# mainBoard.net
KiCad netlist of a schematic drawn in EAGLE
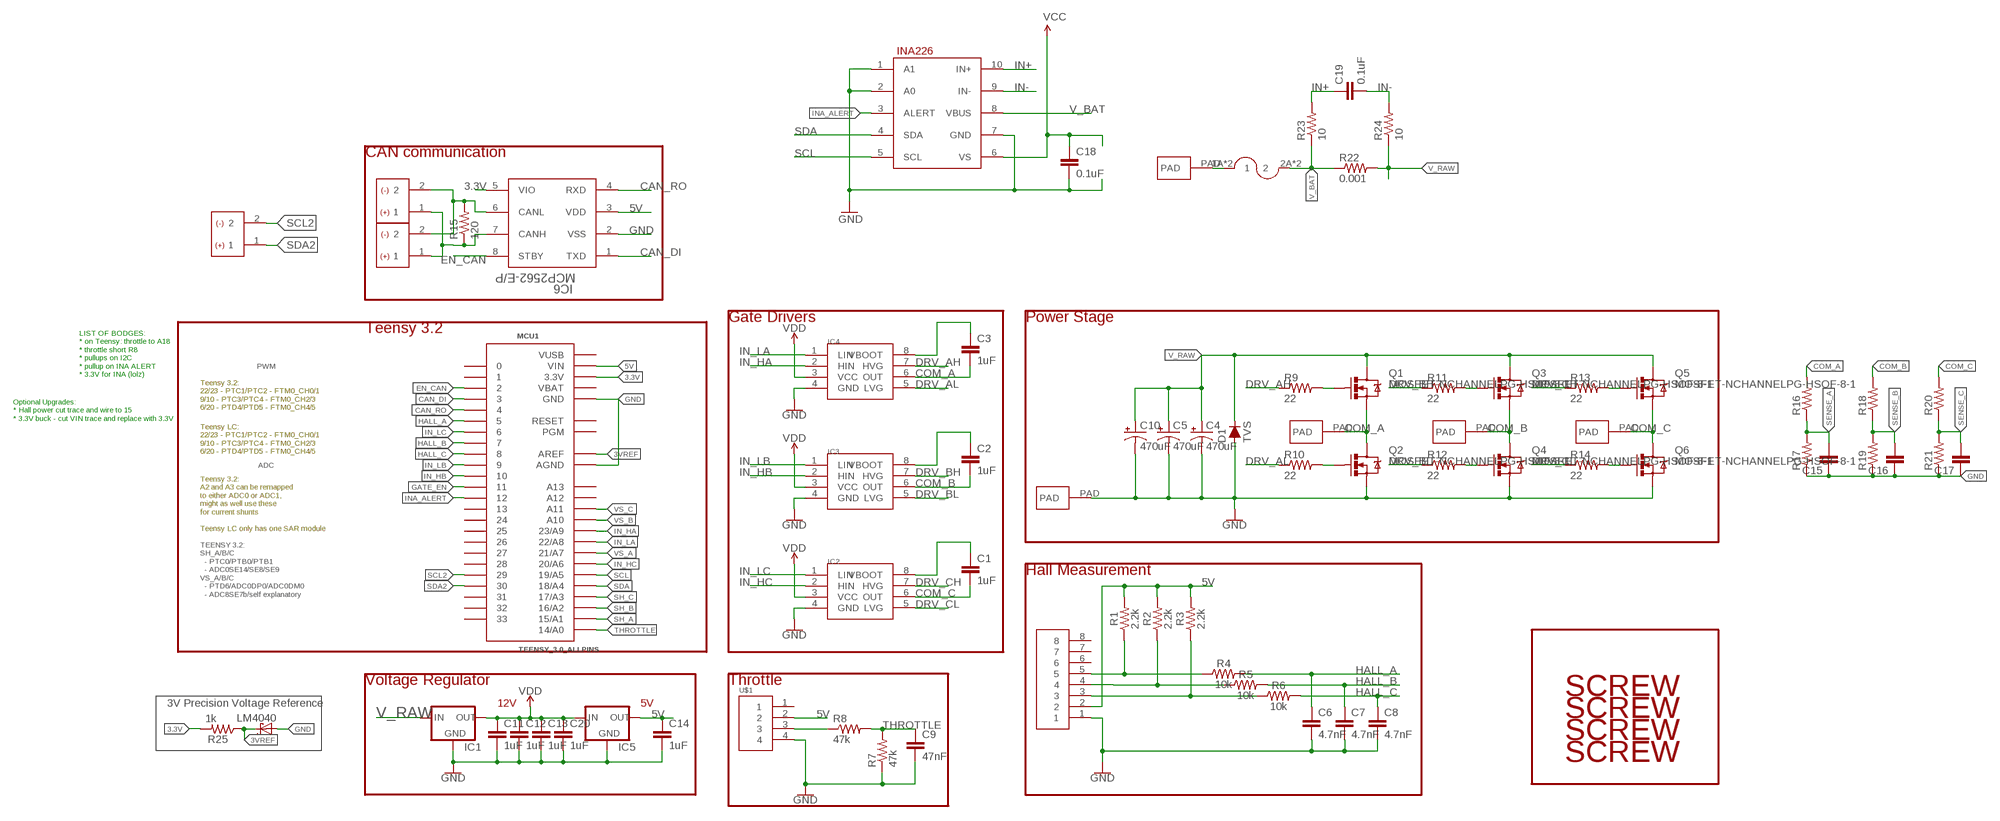
[diagram p0: schematic, sheet 1, part 1 of 2]
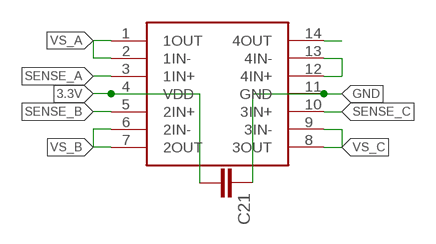
[diagram p1: schematic, sheet 1, part 2 of 2]

(export (version "E")
  (design (tool "Eeschema 10.0.6"))
  (components
    (comp (ref "C1")
      (value "1uF")
      (footprint "eagle-import:CAP-PTH-SMALL-KIT")
      (libsource (lib "eagle-import") (part "CAPKIT"))
    )
    (comp (ref "C2")
      (value "1uF")
      (footprint "eagle-import:CAP-PTH-SMALL-KIT")
      (libsource (lib "eagle-import") (part "CAPKIT"))
    )
    (comp (ref "C3")
      (value "1uF")
      (footprint "eagle-import:CAP-PTH-SMALL-KIT")
      (libsource (lib "eagle-import") (part "CAPKIT"))
    )
    (comp (ref "C4")
      (value "470uF")
      (footprint "eagle-import:CPOL-RADIAL-5MM-10MM")
      (libsource (lib "eagle-import") (part "1000UF-RADIAL-5MM-25V-20%"))
    )
    (comp (ref "C5")
      (value "470uF")
      (footprint "eagle-import:CPOL-RADIAL-5MM-10MM")
      (libsource (lib "eagle-import") (part "1000UF-RADIAL-5MM-25V-20%"))
    )
    (comp (ref "C6")
      (value "4.7nF")
      (footprint "eagle-import:0603-CAP")
      (libsource (lib "eagle-import") (part "SparkFun-Passives_CAP0603-CAP"))
    )
    (comp (ref "C7")
      (value "4.7nF")
      (footprint "eagle-import:0603-CAP")
      (libsource (lib "eagle-import") (part "SparkFun-Passives_CAP0603-CAP"))
    )
    (comp (ref "C8")
      (value "4.7nF")
      (footprint "eagle-import:0603-CAP")
      (libsource (lib "eagle-import") (part "SparkFun-Passives_CAP0603-CAP"))
    )
    (comp (ref "C9")
      (value "47nF")
      (footprint "eagle-import:0603-CAP")
      (libsource (lib "eagle-import") (part "SparkFun-Passives_CAP0603-CAP"))
    )
    (comp (ref "C10")
      (value "470uF")
      (footprint "eagle-import:CPOL-RADIAL-5MM-10MM")
      (libsource (lib "eagle-import") (part "1000UF-RADIAL-5MM-25V-20%"))
    )
    (comp (ref "C11")
      (value "1uF")
      (footprint "eagle-import:CAP-PTH-SMALL-KIT")
      (libsource (lib "eagle-import") (part "CAPKIT"))
    )
    (comp (ref "C12")
      (value "1uF")
      (footprint "eagle-import:CAP-PTH-SMALL-KIT")
      (libsource (lib "eagle-import") (part "CAPKIT"))
    )
    (comp (ref "C13")
      (value "1uF")
      (footprint "eagle-import:CAP-PTH-SMALL-KIT")
      (libsource (lib "eagle-import") (part "CAPKIT"))
    )
    (comp (ref "C14")
      (value "1uF")
      (footprint "eagle-import:CAP-PTH-SMALL-KIT")
      (libsource (lib "eagle-import") (part "CAPKIT"))
    )
    (comp (ref "C15")
      (value "CAP0603-CAP")
      (footprint "eagle-import:0603-CAP")
      (libsource (lib "eagle-import") (part "SparkFun-Passives_CAP0603-CAP"))
    )
    (comp (ref "C16")
      (value "CAP0603-CAP")
      (footprint "eagle-import:0603-CAP")
      (libsource (lib "eagle-import") (part "SparkFun-Passives_CAP0603-CAP"))
    )
    (comp (ref "C17")
      (value "CAP0603-CAP")
      (footprint "eagle-import:0603-CAP")
      (libsource (lib "eagle-import") (part "SparkFun-Passives_CAP0603-CAP"))
    )
    (comp (ref "C18")
      (value "0.1uF")
      (footprint "eagle-import:0603-CAP")
      (libsource (lib "eagle-import") (part "SparkFun-Passives_CAP0603-CAP"))
    )
    (comp (ref "C19")
      (value "0.1uF")
      (footprint "eagle-import:0603-CAP")
      (libsource (lib "eagle-import") (part "SparkFun-Passives_CAP0603-CAP"))
    )
    (comp (ref "C20")
      (value "1uF")
      (footprint "eagle-import:CAP-PTH-SMALL-KIT")
      (libsource (lib "eagle-import") (part "CAPKIT"))
    )
    (comp (ref "C21")
      (value "CAP0603-CAP")
      (footprint "eagle-import:0603-CAP")
      (libsource (lib "eagle-import") (part "SparkFun-Passives_CAP0603-CAP"))
    )
    (comp (ref "CAN1")
      (value "HEADER2")
      (footprint "eagle-import:2PINVALULOK")
      (libsource (lib "eagle-import") (part "HEADER2"))
    )
    (comp (ref "CAN2")
      (value "HEADER2")
      (footprint "eagle-import:2PINVALULOK")
      (libsource (lib "eagle-import") (part "HEADER2"))
    )
    (comp (ref "D1")
      (value "TVS")
      (footprint "eagle-import:DIODE-1N4001")
      (libsource (lib "eagle-import") (part "DIODE-PTH"))
    )
    (comp (ref "I2C")
      (value "HEADER2")
      (footprint "eagle-import:2PINVALULOK")
      (libsource (lib "eagle-import") (part "HEADER2"))
    )
    (comp (ref "IC1")
      (value "V_REG_78XX")
      (footprint "eagle-import:V78W_BACKWARDS")
      (libsource (lib "eagle-import") (part "V_REG_78XX"))
    )
    (comp (ref "IC2")
      (value "L6387EDIP8")
      (footprint "eagle-import:DIP762W53P254L1092H508Q8B")
      (libsource (lib "eagle-import") (part "L6387EDIP8"))
    )
    (comp (ref "IC3")
      (value "L6387EDIP8")
      (footprint "eagle-import:DIP762W53P254L1092H508Q8B")
      (libsource (lib "eagle-import") (part "L6387EDIP8"))
    )
    (comp (ref "IC4")
      (value "L6387EDIP8")
      (footprint "eagle-import:DIP762W53P254L1092H508Q8B")
      (libsource (lib "eagle-import") (part "L6387EDIP8"))
    )
    (comp (ref "IC5")
      (value "V_REG_78XXV78W")
      (footprint "eagle-import:V78W")
      (libsource (lib "eagle-import") (part "V_REG_78XXV78W"))
    )
    (comp (ref "IC6")
      (value "MCP2562-E/P")
      (footprint "eagle-import:PDIP8_300MC")
      (fields (field (name "MANUFACTURER_PART_NUMBER") "MCP2562EP"))
      (libsource (lib "eagle-import") (part "MCP2562-E/P"))
    )
    (comp (ref "IC7")
      (value "INA226")
      (footprint "eagle-import:PSOP-10")
      (libsource (lib "eagle-import") (part "INA226"))
    )
    (comp (ref "J3")
      (value "FUSE")
      (footprint "eagle-import:AUTO_FUSE")
      (libsource (lib "eagle-import") (part "FUSE"))
    )
    (comp (ref "MCU1")
      (value "TEENSY_3.0_ALLPINS")
      (footprint "eagle-import:TEENSY_3.0_ALLPINS")
      (libsource (lib "eagle-import") (part "TEENSY_3.0_ALLPINS"))
    )
    (comp (ref "Q1")
      (value "MOSFET-NCHANNELPG-HSOF-8-1")
      (footprint "eagle-import:PG-HSOF-8-1")
      (libsource (lib "eagle-import") (part "MOSFET-NCHANNELPG-HSOF-8-1"))
    )
    (comp (ref "Q2")
      (value "MOSFET-NCHANNELPG-HSOF-8-1")
      (footprint "eagle-import:PG-HSOF-8-1")
      (libsource (lib "eagle-import") (part "MOSFET-NCHANNELPG-HSOF-8-1"))
    )
    (comp (ref "Q3")
      (value "MOSFET-NCHANNELPG-HSOF-8-1")
      (footprint "eagle-import:PG-HSOF-8-1")
      (libsource (lib "eagle-import") (part "MOSFET-NCHANNELPG-HSOF-8-1"))
    )
    (comp (ref "Q4")
      (value "MOSFET-NCHANNELPG-HSOF-8-1")
      (footprint "eagle-import:PG-HSOF-8-1")
      (libsource (lib "eagle-import") (part "MOSFET-NCHANNELPG-HSOF-8-1"))
    )
    (comp (ref "Q5")
      (value "MOSFET-NCHANNELPG-HSOF-8-1")
      (footprint "eagle-import:PG-HSOF-8-1")
      (libsource (lib "eagle-import") (part "MOSFET-NCHANNELPG-HSOF-8-1"))
    )
    (comp (ref "Q6")
      (value "MOSFET-NCHANNELPG-HSOF-8-1")
      (footprint "eagle-import:PG-HSOF-8-1")
      (libsource (lib "eagle-import") (part "MOSFET-NCHANNELPG-HSOF-8-1"))
    )
    (comp (ref "R1")
      (value "2.2k")
      (footprint "eagle-import:0603")
      (libsource (lib "eagle-import") (part "SparkFun-Resistors_532_RESISTOR0603"))
    )
    (comp (ref "R2")
      (value "2.2k")
      (footprint "eagle-import:0603")
      (libsource (lib "eagle-import") (part "SparkFun-Resistors_532_RESISTOR0603"))
    )
    (comp (ref "R3")
      (value "2.2k")
      (footprint "eagle-import:0603")
      (libsource (lib "eagle-import") (part "SparkFun-Resistors_532_RESISTOR0603"))
    )
    (comp (ref "R4")
      (value "10k")
      (footprint "eagle-import:0603")
      (libsource (lib "eagle-import") (part "SparkFun-Resistors_532_RESISTOR0603"))
    )
    (comp (ref "R5")
      (value "10k")
      (footprint "eagle-import:0603")
      (libsource (lib "eagle-import") (part "SparkFun-Resistors_532_RESISTOR0603"))
    )
    (comp (ref "R6")
      (value "10k")
      (footprint "eagle-import:0603")
      (libsource (lib "eagle-import") (part "SparkFun-Resistors_532_RESISTOR0603"))
    )
    (comp (ref "R7")
      (value "47k")
      (footprint "eagle-import:0603-RES")
      (libsource (lib "eagle-import") (part "RESISTOR0603-RES"))
    )
    (comp (ref "R8")
      (value "47k")
      (footprint "eagle-import:0603-RES")
      (libsource (lib "eagle-import") (part "RESISTOR0603-RES"))
    )
    (comp (ref "R9")
      (value "22")
      (footprint "eagle-import:0603-RES")
      (libsource (lib "eagle-import") (part "RESISTOR0603-RES"))
    )
    (comp (ref "R10")
      (value "22")
      (footprint "eagle-import:0603-RES")
      (libsource (lib "eagle-import") (part "RESISTOR0603-RES"))
    )
    (comp (ref "R11")
      (value "22")
      (footprint "eagle-import:0603-RES")
      (libsource (lib "eagle-import") (part "RESISTOR0603-RES"))
    )
    (comp (ref "R12")
      (value "22")
      (footprint "eagle-import:0603-RES")
      (libsource (lib "eagle-import") (part "RESISTOR0603-RES"))
    )
    (comp (ref "R13")
      (value "22")
      (footprint "eagle-import:0603-RES")
      (libsource (lib "eagle-import") (part "RESISTOR0603-RES"))
    )
    (comp (ref "R14")
      (value "22")
      (footprint "eagle-import:0603-RES")
      (libsource (lib "eagle-import") (part "RESISTOR0603-RES"))
    )
    (comp (ref "R15")
      (value "120")
      (footprint "eagle-import:0603-RES")
      (libsource (lib "eagle-import") (part "RESISTOR0603-RES"))
    )
    (comp (ref "R16")
      (value "RESISTOR0603-RES")
      (footprint "eagle-import:0603-RES")
      (libsource (lib "eagle-import") (part "RESISTOR0603-RES"))
    )
    (comp (ref "R17")
      (value "RESISTOR0603-RES")
      (footprint "eagle-import:0603-RES")
      (libsource (lib "eagle-import") (part "RESISTOR0603-RES"))
    )
    (comp (ref "R18")
      (value "RESISTOR0603-RES")
      (footprint "eagle-import:0603-RES")
      (libsource (lib "eagle-import") (part "RESISTOR0603-RES"))
    )
    (comp (ref "R19")
      (value "RESISTOR0603-RES")
      (footprint "eagle-import:0603-RES")
      (libsource (lib "eagle-import") (part "RESISTOR0603-RES"))
    )
    (comp (ref "R20")
      (value "RESISTOR0603-RES")
      (footprint "eagle-import:0603-RES")
      (libsource (lib "eagle-import") (part "RESISTOR0603-RES"))
    )
    (comp (ref "R21")
      (value "RESISTOR0603-RES")
      (footprint "eagle-import:0603-RES")
      (libsource (lib "eagle-import") (part "RESISTOR0603-RES"))
    )
    (comp (ref "R22")
      (value "0.001")
      (footprint "eagle-import:R2512")
      (libsource (lib "eagle-import") (part "SparkFun-Resistors_RESISTOR2512"))
    )
    (comp (ref "R23")
      (value "10")
      (footprint "eagle-import:0603-RES")
      (libsource (lib "eagle-import") (part "RESISTOR0603-RES"))
    )
    (comp (ref "R24")
      (value "10")
      (footprint "eagle-import:0603-RES")
      (libsource (lib "eagle-import") (part "RESISTOR0603-RES"))
    )
    (comp (ref "R25")
      (value "1k")
      (footprint "eagle-import:0603-RES")
      (libsource (lib "eagle-import") (part "RESISTOR0603-RES"))
    )
    (comp (ref "U$1")
      (value "HEADER4VALULOK")
      (footprint "eagle-import:4PINVALULOK")
      (libsource (lib "eagle-import") (part "HEADER4VALULOK"))
    )
    (comp (ref "U$2")
      (value "OPAMP_QUAD")
      (footprint "eagle-import:TSSOP-14")
      (libsource (lib "eagle-import") (part "OPAMP_QUAD"))
    )
    (comp (ref "U$4")
      (value "PAD")
      (footprint "eagle-import:PAD")
      (libsource (lib "eagle-import") (part "PAD"))
    )
    (comp (ref "U$5")
      (value "PAD")
      (footprint "eagle-import:PAD")
      (libsource (lib "eagle-import") (part "PAD"))
    )
    (comp (ref "U$6")
      (value "PAD")
      (footprint "eagle-import:PAD")
      (libsource (lib "eagle-import") (part "PAD"))
    )
    (comp (ref "U$7")
      (value "PAD")
      (footprint "eagle-import:PAD")
      (libsource (lib "eagle-import") (part "PAD"))
    )
    (comp (ref "U$8")
      (value "PAD")
      (footprint "eagle-import:PAD")
      (libsource (lib "eagle-import") (part "PAD"))
    )
    (comp (ref "U$10")
      (value "SCREW")
      (footprint "eagle-import:M3HOLE")
      (libsource (lib "eagle-import") (part "SCREW"))
    )
    (comp (ref "U$11")
      (value "SCREW")
      (footprint "eagle-import:M3HOLE")
      (libsource (lib "eagle-import") (part "SCREW"))
    )
    (comp (ref "U$12")
      (value "SCREW")
      (footprint "eagle-import:M3HOLE")
      (libsource (lib "eagle-import") (part "SCREW"))
    )
    (comp (ref "U$13")
      (value "SCREW")
      (footprint "eagle-import:M3HOLE")
      (libsource (lib "eagle-import") (part "SCREW"))
    )
    (comp (ref "U$14")
      (value "HEADER8")
      (footprint "eagle-import:8PINVALULOK")
      (libsource (lib "eagle-import") (part "HEADER8"))
    )
    (comp (ref "U$15")
      (value "LM4040")
      (footprint "eagle-import:SOT23-3")
      (libsource (lib "eagle-import") (part "LM4040"))
    )
  )
  (nets
    (net (code "1") (name "/DRV_AH") (class "Default")
      (node (ref "IC4") (pin "7") (pinfunction "HVG_7") (pintype "bidirectional"))
      (node (ref "R9") (pin "1") (pinfunction "1_1") (pintype "passive"))
    )
    (net (code "2") (name "/DRV_AL") (class "Default")
      (node (ref "IC4") (pin "5") (pinfunction "LVG_5") (pintype "bidirectional"))
      (node (ref "R10") (pin "1") (pinfunction "1_1") (pintype "passive"))
    )
    (net (code "3") (name "/DRV_BH") (class "Default")
      (node (ref "IC3") (pin "7") (pinfunction "HVG_7") (pintype "bidirectional"))
      (node (ref "R11") (pin "1") (pinfunction "1_1") (pintype "passive"))
    )
    (net (code "4") (name "/DRV_BL") (class "Default")
      (node (ref "IC3") (pin "5") (pinfunction "LVG_5") (pintype "bidirectional"))
      (node (ref "R12") (pin "1") (pinfunction "1_1") (pintype "passive"))
    )
    (net (code "5") (name "/DRV_CH") (class "Default")
      (node (ref "IC2") (pin "7") (pinfunction "HVG_7") (pintype "bidirectional"))
      (node (ref "R13") (pin "1") (pinfunction "1_1") (pintype "passive"))
    )
    (net (code "6") (name "/DRV_CL") (class "Default")
      (node (ref "IC2") (pin "5") (pinfunction "LVG_5") (pintype "bidirectional"))
      (node (ref "R14") (pin "1") (pinfunction "1_1") (pintype "passive"))
    )
    (net (code "7") (name "/IN+") (class "Default")
      (node (ref "C19") (pin "1") (pinfunction "1_1") (pintype "passive"))
      (node (ref "IC7") (pin "10") (pinfunction "IN+_10") (pintype "bidirectional"))
      (node (ref "R23") (pin "2") (pinfunction "2_2") (pintype "passive"))
    )
    (net (code "8") (name "/IN-") (class "Default")
      (node (ref "C19") (pin "2") (pinfunction "2_2") (pintype "passive"))
      (node (ref "IC7") (pin "9") (pinfunction "IN-_9") (pintype "bidirectional"))
      (node (ref "R24") (pin "2") (pinfunction "2_2") (pintype "passive"))
    )
    (net (code "9") (name "/VBAT") (class "Default")
      (node (ref "MCU1") (pin "VBAT") (pinfunction "VBAT_VBAT") (pintype "power_in"))
    )
    (net (code "10") (name "/VUSB") (class "Default")
      (node (ref "MCU1") (pin "VUSB") (pinfunction "VUSB_VUSB") (pintype "power_in"))
    )
    (net (code "11") (name "3.3V") (class "Default")
      (node (ref "C21") (pin "2") (pinfunction "2_2") (pintype "passive"))
      (node (ref "IC6") (pin "5") (pinfunction "VIO_5") (pintype "passive"))
      (node (ref "MCU1") (pin "3.3V") (pinfunction "3.3V_3.3V") (pintype "power_in"))
      (node (ref "MCU1") (pin "3.3V1") (pinfunction "3.3V_3.3V1") (pintype "power_in"))
      (node (ref "MCU1") (pin "3.3V2") (pinfunction "3.3V_3.3V2") (pintype "power_in"))
      (node (ref "R25") (pin "2") (pinfunction "2_2") (pintype "passive"))
      (node (ref "U$2") (pin "4") (pinfunction "VDD_4") (pintype "bidirectional"))
    )
    (net (code "12") (name "3VREF") (class "Default")
      (node (ref "MCU1") (pin "AREF") (pinfunction "AREF_AREF") (pintype "power_in"))
      (node (ref "R25") (pin "1") (pinfunction "1_1") (pintype "passive"))
      (node (ref "U$15") (pin "1") (pinfunction "C_1") (pintype "passive"))
    )
    (net (code "13") (name "5V") (class "Default")
      (node (ref "C14") (pin "1") (pinfunction "1_1") (pintype "passive"))
      (node (ref "IC5") (pin "OUT") (pinfunction "OUT_OUT") (pintype "output"))
      (node (ref "IC6") (pin "3") (pinfunction "VDD_3") (pintype "power_in"))
      (node (ref "MCU1") (pin "VIN") (pinfunction "VIN_VIN") (pintype "power_in"))
      (node (ref "R1") (pin "2") (pinfunction "2_2") (pintype "passive"))
      (node (ref "R2") (pin "2") (pinfunction "2_2") (pintype "passive"))
      (node (ref "R3") (pin "2") (pinfunction "2_2") (pintype "passive"))
      (node (ref "U$1") (pin "2") (pinfunction "2_2") (pintype "bidirectional"))
      (node (ref "U$14") (pin "2") (pinfunction "2_2") (pintype "bidirectional"))
    )
    (net (code "14") (name "CAN_DI") (class "Default")
      (node (ref "IC6") (pin "1") (pinfunction "TXD_1") (pintype "input"))
      (node (ref "MCU1") (pin "3") (pinfunction "3_3") (pintype "bidirectional"))
    )
    (net (code "15") (name "CAN_RO") (class "Default")
      (node (ref "IC6") (pin "4") (pinfunction "RXD_4") (pintype "output"))
      (node (ref "MCU1") (pin "4") (pinfunction "4_4") (pintype "bidirectional"))
    )
    (net (code "16") (name "COM_A") (class "Default")
      (node (ref "C3") (pin "2") (pinfunction "2_2") (pintype "passive"))
      (node (ref "IC4") (pin "6") (pinfunction "OUT_6") (pintype "bidirectional"))
      (node (ref "Q1") (pin "S") (pinfunction "S_S") (pintype "passive"))
      (node (ref "Q2") (pin "D") (pinfunction "D_D") (pintype "passive"))
      (node (ref "R16") (pin "2") (pinfunction "2_2") (pintype "passive"))
      (node (ref "U$6") (pin "PAD") (pinfunction "PAD_PAD") (pintype "bidirectional"))
    )
    (net (code "17") (name "COM_B") (class "Default")
      (node (ref "C2") (pin "2") (pinfunction "2_2") (pintype "passive"))
      (node (ref "IC3") (pin "6") (pinfunction "OUT_6") (pintype "bidirectional"))
      (node (ref "Q3") (pin "S") (pinfunction "S_S") (pintype "passive"))
      (node (ref "Q4") (pin "D") (pinfunction "D_D") (pintype "passive"))
      (node (ref "R18") (pin "2") (pinfunction "2_2") (pintype "passive"))
      (node (ref "U$7") (pin "PAD") (pinfunction "PAD_PAD") (pintype "bidirectional"))
    )
    (net (code "18") (name "COM_C") (class "Default")
      (node (ref "C1") (pin "2") (pinfunction "2_2") (pintype "passive"))
      (node (ref "IC2") (pin "6") (pinfunction "OUT_6") (pintype "bidirectional"))
      (node (ref "Q5") (pin "S") (pinfunction "S_S") (pintype "passive"))
      (node (ref "Q6") (pin "D") (pinfunction "D_D") (pintype "passive"))
      (node (ref "R20") (pin "2") (pinfunction "2_2") (pintype "passive"))
      (node (ref "U$8") (pin "PAD") (pinfunction "PAD_PAD") (pintype "bidirectional"))
    )
    (net (code "19") (name "EN_CAN") (class "Default")
      (node (ref "IC6") (pin "8") (pinfunction "STBY_8") (pintype "input"))
      (node (ref "MCU1") (pin "2") (pinfunction "2_2") (pintype "bidirectional"))
    )
    (net (code "20") (name "GATE_EN") (class "Default")
      (node (ref "MCU1") (pin "11") (pinfunction "11_11") (pintype "bidirectional"))
    )
    (net (code "21") (name "GND") (class "Default")
      (node (ref "C10") (pin "-") (pinfunction "-_-") (pintype "passive"))
      (node (ref "C11") (pin "2") (pinfunction "2_2") (pintype "passive"))
      (node (ref "C12") (pin "2") (pinfunction "2_2") (pintype "passive"))
      (node (ref "C13") (pin "2") (pinfunction "2_2") (pintype "passive"))
      (node (ref "C14") (pin "2") (pinfunction "2_2") (pintype "passive"))
      (node (ref "C15") (pin "1") (pinfunction "1_1") (pintype "passive"))
      (node (ref "C16") (pin "1") (pinfunction "1_1") (pintype "passive"))
      (node (ref "C17") (pin "1") (pinfunction "1_1") (pintype "passive"))
      (node (ref "C18") (pin "2") (pinfunction "2_2") (pintype "passive"))
      (node (ref "C20") (pin "2") (pinfunction "2_2") (pintype "passive"))
      (node (ref "C21") (pin "1") (pinfunction "1_1") (pintype "passive"))
      (node (ref "C4") (pin "-") (pinfunction "-_-") (pintype "passive"))
      (node (ref "C5") (pin "-") (pinfunction "-_-") (pintype "passive"))
      (node (ref "C6") (pin "2") (pinfunction "2_2") (pintype "passive"))
      (node (ref "C7") (pin "2") (pinfunction "2_2") (pintype "passive"))
      (node (ref "C8") (pin "2") (pinfunction "2_2") (pintype "passive"))
      (node (ref "C9") (pin "2") (pinfunction "2_2") (pintype "passive"))
      (node (ref "D1") (pin "A") (pinfunction "A_A") (pintype "passive"))
      (node (ref "IC1") (pin "GND") (pinfunction "GND_GND") (pintype "input"))
      (node (ref "IC2") (pin "4") (pinfunction "GND_4") (pintype "bidirectional"))
      (node (ref "IC3") (pin "4") (pinfunction "GND_4") (pintype "bidirectional"))
      (node (ref "IC4") (pin "4") (pinfunction "GND_4") (pintype "bidirectional"))
      (node (ref "IC5") (pin "GND") (pinfunction "GND_GND") (pintype "input"))
      (node (ref "IC6") (pin "2") (pinfunction "VSS_2") (pintype "power_in"))
      (node (ref "IC7") (pin "1") (pinfunction "A1_1") (pintype "bidirectional"))
      (node (ref "IC7") (pin "2") (pinfunction "A0_2") (pintype "bidirectional"))
      (node (ref "IC7") (pin "7") (pinfunction "GND_7") (pintype "bidirectional"))
      (node (ref "MCU1") (pin "AGND") (pinfunction "AGND_AGND") (pintype "power_in"))
      (node (ref "MCU1") (pin "GND") (pinfunction "GND_GND") (pintype "power_in"))
      (node (ref "MCU1") (pin "GND1") (pinfunction "GND_GND1") (pintype "power_in"))
      (node (ref "MCU1") (pin "GND2") (pinfunction "GND_GND2") (pintype "power_in"))
      (node (ref "Q2") (pin "S") (pinfunction "S_S") (pintype "passive"))
      (node (ref "Q4") (pin "S") (pinfunction "S_S") (pintype "passive"))
      (node (ref "Q6") (pin "S") (pinfunction "S_S") (pintype "passive"))
      (node (ref "R17") (pin "1") (pinfunction "1_1") (pintype "passive"))
      (node (ref "R19") (pin "1") (pinfunction "1_1") (pintype "passive"))
      (node (ref "R21") (pin "1") (pinfunction "1_1") (pintype "passive"))
      (node (ref "R7") (pin "1") (pinfunction "1_1") (pintype "passive"))
      (node (ref "U$1") (pin "4") (pinfunction "4_4") (pintype "bidirectional"))
      (node (ref "U$14") (pin "1") (pinfunction "1_1") (pintype "bidirectional"))
      (node (ref "U$15") (pin "2") (pinfunction "A_2") (pintype "passive"))
      (node (ref "U$2") (pin "11") (pinfunction "GND_11") (pintype "bidirectional"))
      (node (ref "U$5") (pin "PAD") (pinfunction "PAD_PAD") (pintype "bidirectional"))
    )
    (net (code "22") (name "HALL_A") (class "Default")
      (node (ref "C6") (pin "1") (pinfunction "1_1") (pintype "passive"))
      (node (ref "MCU1") (pin "5") (pinfunction "5_5") (pintype "bidirectional"))
      (node (ref "R4") (pin "2") (pinfunction "2_2") (pintype "passive"))
    )
    (net (code "23") (name "HALL_B") (class "Default")
      (node (ref "C7") (pin "1") (pinfunction "1_1") (pintype "passive"))
      (node (ref "MCU1") (pin "7") (pinfunction "7_7") (pintype "bidirectional"))
      (node (ref "R5") (pin "2") (pinfunction "2_2") (pintype "passive"))
    )
    (net (code "24") (name "HALL_C") (class "Default")
      (node (ref "C8") (pin "1") (pinfunction "1_1") (pintype "passive"))
      (node (ref "MCU1") (pin "8") (pinfunction "8_8") (pintype "bidirectional"))
      (node (ref "R6") (pin "2") (pinfunction "2_2") (pintype "passive"))
    )
    (net (code "25") (name "INA_ALERT") (class "Default")
      (node (ref "IC7") (pin "3") (pinfunction "ALERT_3") (pintype "bidirectional"))
      (node (ref "MCU1") (pin "12") (pinfunction "12_12") (pintype "bidirectional"))
    )
    (net (code "26") (name "IN_HA") (class "Default")
      (node (ref "IC4") (pin "2") (pinfunction "HIN_2") (pintype "bidirectional"))
      (node (ref "MCU1") (pin "23/A9") (pinfunction "23/A9_23/A9") (pintype "bidirectional"))
    )
    (net (code "27") (name "IN_HB") (class "Default")
      (node (ref "IC3") (pin "2") (pinfunction "HIN_2") (pintype "bidirectional"))
      (node (ref "MCU1") (pin "10") (pinfunction "10_10") (pintype "bidirectional"))
    )
    (net (code "28") (name "IN_HC") (class "Default")
      (node (ref "IC2") (pin "2") (pinfunction "HIN_2") (pintype "bidirectional"))
      (node (ref "MCU1") (pin "20/A6") (pinfunction "20/A6_20/A6") (pintype "bidirectional"))
    )
    (net (code "29") (name "IN_LA") (class "Default")
      (node (ref "IC4") (pin "1") (pinfunction "LIN_1") (pintype "bidirectional"))
      (node (ref "MCU1") (pin "22/A8") (pinfunction "22/A8_22/A8") (pintype "bidirectional"))
    )
    (net (code "30") (name "IN_LB") (class "Default")
      (node (ref "IC3") (pin "1") (pinfunction "LIN_1") (pintype "bidirectional"))
      (node (ref "MCU1") (pin "9") (pinfunction "9_9") (pintype "bidirectional"))
    )
    (net (code "31") (name "IN_LC") (class "Default")
      (node (ref "IC2") (pin "1") (pinfunction "LIN_1") (pintype "bidirectional"))
      (node (ref "MCU1") (pin "6") (pinfunction "6_6") (pintype "bidirectional"))
    )
    (net (code "32") (name "Net-(IC2-VBOOT)") (class "Default")
      (node (ref "C1") (pin "1") (pinfunction "1_1") (pintype "passive"))
      (node (ref "IC2") (pin "8") (pinfunction "VBOOT_8") (pintype "bidirectional"))
    )
    (net (code "33") (name "Net-(IC3-VBOOT)") (class "Default")
      (node (ref "C2") (pin "1") (pinfunction "1_1") (pintype "passive"))
      (node (ref "IC3") (pin "8") (pinfunction "VBOOT_8") (pintype "bidirectional"))
    )
    (net (code "34") (name "Net-(IC4-VBOOT)") (class "Default")
      (node (ref "C3") (pin "1") (pinfunction "1_1") (pintype "passive"))
      (node (ref "IC4") (pin "8") (pinfunction "VBOOT_8") (pintype "bidirectional"))
    )
    (net (code "35") (name "Net-(IC6-CANH)") (class "Default")
      (node (ref "CAN1") (pin "1") (pinfunction "1_1") (pintype "bidirectional"))
      (node (ref "CAN2") (pin "1") (pinfunction "1_1") (pintype "bidirectional"))
      (node (ref "IC6") (pin "7") (pinfunction "CANH_7") (pintype "bidirectional"))
      (node (ref "R15") (pin "1") (pinfunction "1_1") (pintype "passive"))
    )
    (net (code "36") (name "Net-(IC6-CANL)") (class "Default")
      (node (ref "CAN1") (pin "2") (pinfunction "2_2") (pintype "bidirectional"))
      (node (ref "CAN2") (pin "2") (pinfunction "2_2") (pintype "bidirectional"))
      (node (ref "IC6") (pin "6") (pinfunction "CANL_6") (pintype "bidirectional"))
      (node (ref "R15") (pin "2") (pinfunction "2_2") (pintype "passive"))
    )
    (net (code "37") (name "Net-(J3-1-Pad1A)") (class "Default")
      (node (ref "J3") (pin "1A") (pinfunction "1_1A") (pintype "bidirectional"))
      (node (ref "J3") (pin "1B") (pinfunction "1_1B") (pintype "bidirectional"))
      (node (ref "U$4") (pin "PAD") (pinfunction "PAD_PAD") (pintype "bidirectional"))
    )
    (net (code "38") (name "Net-(Q1-PadG)") (class "Default")
      (node (ref "Q1") (pin "G") (pinfunction "G_G") (pintype "passive"))
      (node (ref "R9") (pin "2") (pinfunction "2_2") (pintype "passive"))
    )
    (net (code "39") (name "Net-(Q2-PadG)") (class "Default")
      (node (ref "Q2") (pin "G") (pinfunction "G_G") (pintype "passive"))
      (node (ref "R10") (pin "2") (pinfunction "2_2") (pintype "passive"))
    )
    (net (code "40") (name "Net-(Q3-PadG)") (class "Default")
      (node (ref "Q3") (pin "G") (pinfunction "G_G") (pintype "passive"))
      (node (ref "R11") (pin "2") (pinfunction "2_2") (pintype "passive"))
    )
    (net (code "41") (name "Net-(Q4-PadG)") (class "Default")
      (node (ref "Q4") (pin "G") (pinfunction "G_G") (pintype "passive"))
      (node (ref "R12") (pin "2") (pinfunction "2_2") (pintype "passive"))
    )
    (net (code "42") (name "Net-(Q5-PadG)") (class "Default")
      (node (ref "Q5") (pin "G") (pinfunction "G_G") (pintype "passive"))
      (node (ref "R13") (pin "2") (pinfunction "2_2") (pintype "passive"))
    )
    (net (code "43") (name "Net-(Q6-PadG)") (class "Default")
      (node (ref "Q6") (pin "G") (pinfunction "G_G") (pintype "passive"))
      (node (ref "R14") (pin "2") (pinfunction "2_2") (pintype "passive"))
    )
    (net (code "44") (name "Net-(R1-Pad1)") (class "Default")
      (node (ref "R1") (pin "1") (pinfunction "1_1") (pintype "passive"))
      (node (ref "R4") (pin "1") (pinfunction "1_1") (pintype "passive"))
      (node (ref "U$14") (pin "5") (pinfunction "5_5") (pintype "bidirectional"))
    )
    (net (code "45") (name "Net-(R2-Pad1)") (class "Default")
      (node (ref "R2") (pin "1") (pinfunction "1_1") (pintype "passive"))
      (node (ref "R5") (pin "1") (pinfunction "1_1") (pintype "passive"))
      (node (ref "U$14") (pin "4") (pinfunction "4_4") (pintype "bidirectional"))
    )
    (net (code "46") (name "Net-(R3-Pad1)") (class "Default")
      (node (ref "R3") (pin "1") (pinfunction "1_1") (pintype "passive"))
      (node (ref "R6") (pin "1") (pinfunction "1_1") (pintype "passive"))
      (node (ref "U$14") (pin "3") (pinfunction "3_3") (pintype "bidirectional"))
    )
    (net (code "47") (name "Net-(R8-Pad1)") (class "Default")
      (node (ref "R8") (pin "1") (pinfunction "1_1") (pintype "passive"))
      (node (ref "U$1") (pin "3") (pinfunction "3_3") (pintype "bidirectional"))
    )
    (net (code "48") (name "Net-(U$2-4IN+)") (class "Default")
      (node (ref "U$2") (pin "12") (pinfunction "4IN+_12") (pintype "bidirectional"))
      (node (ref "U$2") (pin "13") (pinfunction "4IN-_13") (pintype "bidirectional"))
    )
    (net (code "49") (name "SCL") (class "Default")
      (node (ref "IC7") (pin "5") (pinfunction "SCL_5") (pintype "bidirectional"))
      (node (ref "MCU1") (pin "19/A5") (pinfunction "19/A5_19/A5") (pintype "bidirectional"))
    )
    (net (code "50") (name "SCL2") (class "Default")
      (node (ref "I2C") (pin "2") (pinfunction "2_2") (pintype "bidirectional"))
      (node (ref "MCU1") (pin "29") (pinfunction "29_29") (pintype "bidirectional"))
    )
    (net (code "51") (name "SDA") (class "Default")
      (node (ref "IC7") (pin "4") (pinfunction "SDA_4") (pintype "bidirectional"))
      (node (ref "MCU1") (pin "18/A4") (pinfunction "18/A4_18/A4") (pintype "bidirectional"))
    )
    (net (code "52") (name "SDA2") (class "Default")
      (node (ref "I2C") (pin "1") (pinfunction "1_1") (pintype "bidirectional"))
      (node (ref "MCU1") (pin "30") (pinfunction "30_30") (pintype "bidirectional"))
    )
    (net (code "53") (name "SENSE_A") (class "Default")
      (node (ref "C15") (pin "2") (pinfunction "2_2") (pintype "passive"))
      (node (ref "R16") (pin "1") (pinfunction "1_1") (pintype "passive"))
      (node (ref "R17") (pin "2") (pinfunction "2_2") (pintype "passive"))
      (node (ref "U$2") (pin "3") (pinfunction "1IN+_3") (pintype "bidirectional"))
    )
    (net (code "54") (name "SENSE_B") (class "Default")
      (node (ref "C16") (pin "2") (pinfunction "2_2") (pintype "passive"))
      (node (ref "R18") (pin "1") (pinfunction "1_1") (pintype "passive"))
      (node (ref "R19") (pin "2") (pinfunction "2_2") (pintype "passive"))
      (node (ref "U$2") (pin "5") (pinfunction "2IN+_5") (pintype "bidirectional"))
    )
    (net (code "55") (name "SENSE_C") (class "Default")
      (node (ref "C17") (pin "2") (pinfunction "2_2") (pintype "passive"))
      (node (ref "R20") (pin "1") (pinfunction "1_1") (pintype "passive"))
      (node (ref "R21") (pin "2") (pinfunction "2_2") (pintype "passive"))
      (node (ref "U$2") (pin "10") (pinfunction "3IN+_10") (pintype "bidirectional"))
    )
    (net (code "56") (name "SH_A") (class "Default")
      (node (ref "MCU1") (pin "15/A1") (pinfunction "15/A1_15/A1") (pintype "bidirectional"))
    )
    (net (code "57") (name "SH_B") (class "Default")
      (node (ref "MCU1") (pin "16/A2") (pinfunction "16/A2_16/A2") (pintype "bidirectional"))
    )
    (net (code "58") (name "SH_C") (class "Default")
      (node (ref "MCU1") (pin "17/A3") (pinfunction "17/A3_17/A3") (pintype "bidirectional"))
    )
    (net (code "59") (name "THROTTLE") (class "Default")
      (node (ref "C9") (pin "1") (pinfunction "1_1") (pintype "passive"))
      (node (ref "MCU1") (pin "14/A0") (pinfunction "14/A0_14/A0") (pintype "bidirectional"))
      (node (ref "R7") (pin "2") (pinfunction "2_2") (pintype "passive"))
      (node (ref "R8") (pin "2") (pinfunction "2_2") (pintype "passive"))
    )
    (net (code "60") (name "VCC") (class "Default")
      (node (ref "C18") (pin "1") (pinfunction "1_1") (pintype "passive"))
      (node (ref "IC7") (pin "6") (pinfunction "VS_6") (pintype "bidirectional"))
    )
    (net (code "61") (name "VDD") (class "Default")
      (node (ref "C11") (pin "1") (pinfunction "1_1") (pintype "passive"))
      (node (ref "C12") (pin "1") (pinfunction "1_1") (pintype "passive"))
      (node (ref "C13") (pin "1") (pinfunction "1_1") (pintype "passive"))
      (node (ref "C20") (pin "1") (pinfunction "1_1") (pintype "passive"))
      (node (ref "IC1") (pin "OUT") (pinfunction "OUT_OUT") (pintype "output"))
      (node (ref "IC2") (pin "3") (pinfunction "VCC_3") (pintype "bidirectional"))
      (node (ref "IC3") (pin "3") (pinfunction "VCC_3") (pintype "bidirectional"))
      (node (ref "IC4") (pin "3") (pinfunction "VCC_3") (pintype "bidirectional"))
      (node (ref "IC5") (pin "IN") (pinfunction "IN_IN") (pintype "input"))
    )
    (net (code "62") (name "VS_A") (class "Default")
      (node (ref "MCU1") (pin "21/A7") (pinfunction "21/A7_21/A7") (pintype "bidirectional"))
      (node (ref "U$2") (pin "1") (pinfunction "1OUT_1") (pintype "bidirectional"))
      (node (ref "U$2") (pin "2") (pinfunction "1IN-_2") (pintype "bidirectional"))
    )
    (net (code "63") (name "VS_B") (class "Default")
      (node (ref "MCU1") (pin "A10") (pinfunction "A10_A10") (pintype "bidirectional"))
      (node (ref "U$2") (pin "6") (pinfunction "2IN-_6") (pintype "bidirectional"))
      (node (ref "U$2") (pin "7") (pinfunction "2OUT_7") (pintype "bidirectional"))
    )
    (net (code "64") (name "VS_C") (class "Default")
      (node (ref "MCU1") (pin "A11") (pinfunction "A11_A11") (pintype "bidirectional"))
      (node (ref "U$2") (pin "8") (pinfunction "3OUT_8") (pintype "bidirectional"))
      (node (ref "U$2") (pin "9") (pinfunction "3IN-_9") (pintype "bidirectional"))
    )
    (net (code "65") (name "V_BAT") (class "Default")
      (node (ref "IC7") (pin "8") (pinfunction "VBUS_8") (pintype "bidirectional"))
      (node (ref "J3") (pin "2A") (pinfunction "2_2A") (pintype "bidirectional"))
      (node (ref "J3") (pin "2B") (pinfunction "2_2B") (pintype "bidirectional"))
      (node (ref "R22") (pin "1") (pinfunction "1_1") (pintype "passive"))
      (node (ref "R23") (pin "1") (pinfunction "1_1") (pintype "passive"))
    )
    (net (code "66") (name "V_RAW") (class "Default")
      (node (ref "C10") (pin "+") (pinfunction "+_+") (pintype "passive"))
      (node (ref "C4") (pin "+") (pinfunction "+_+") (pintype "passive"))
      (node (ref "C5") (pin "+") (pinfunction "+_+") (pintype "passive"))
      (node (ref "D1") (pin "C") (pinfunction "C_C") (pintype "passive"))
      (node (ref "IC1") (pin "IN") (pinfunction "IN_IN") (pintype "input"))
      (node (ref "Q1") (pin "D") (pinfunction "D_D") (pintype "passive"))
      (node (ref "Q3") (pin "D") (pinfunction "D_D") (pintype "passive"))
      (node (ref "Q5") (pin "D") (pinfunction "D_D") (pintype "passive"))
      (node (ref "R22") (pin "2") (pinfunction "2_2") (pintype "passive"))
      (node (ref "R24") (pin "1") (pinfunction "1_1") (pintype "passive"))
    )
    (net (code "67") (name "unconnected-(MCU1-Pad0)") (class "Default")
      (node (ref "MCU1") (pin "0") (pinfunction "0_0") (pintype "bidirectional"))
    )
    (net (code "68") (name "unconnected-(MCU1-Pad1)") (class "Default")
      (node (ref "MCU1") (pin "1") (pinfunction "1_1") (pintype "bidirectional"))
    )
    (net (code "69") (name "unconnected-(MCU1-Pad13)") (class "Default")
      (node (ref "MCU1") (pin "13") (pinfunction "13_13") (pintype "bidirectional"))
    )
    (net (code "70") (name "unconnected-(MCU1-Pad24)") (class "Default")
      (node (ref "MCU1") (pin "24") (pinfunction "24_24") (pintype "bidirectional"))
    )
    (net (code "71") (name "unconnected-(MCU1-Pad25)") (class "Default")
      (node (ref "MCU1") (pin "25") (pinfunction "25_25") (pintype "bidirectional"))
    )
    (net (code "72") (name "unconnected-(MCU1-Pad26)") (class "Default")
      (node (ref "MCU1") (pin "26") (pinfunction "26_26") (pintype "bidirectional"))
    )
    (net (code "73") (name "unconnected-(MCU1-Pad27)") (class "Default")
      (node (ref "MCU1") (pin "27") (pinfunction "27_27") (pintype "bidirectional"))
    )
    (net (code "74") (name "unconnected-(MCU1-Pad28)") (class "Default")
      (node (ref "MCU1") (pin "28") (pinfunction "28_28") (pintype "bidirectional"))
    )
    (net (code "75") (name "unconnected-(MCU1-Pad31)") (class "Default")
      (node (ref "MCU1") (pin "31") (pinfunction "31_31") (pintype "bidirectional"))
    )
    (net (code "76") (name "unconnected-(MCU1-Pad32)") (class "Default")
      (node (ref "MCU1") (pin "32") (pinfunction "32_32") (pintype "bidirectional"))
    )
    (net (code "77") (name "unconnected-(MCU1-Pad33)") (class "Default")
      (node (ref "MCU1") (pin "33") (pinfunction "33_33") (pintype "bidirectional"))
    )
    (net (code "78") (name "unconnected-(MCU1-PadA12)") (class "Default")
      (node (ref "MCU1") (pin "A12") (pinfunction "A12_A12") (pintype "bidirectional"))
    )
    (net (code "79") (name "unconnected-(MCU1-PadA13)") (class "Default")
      (node (ref "MCU1") (pin "A13") (pinfunction "A13_A13") (pintype "bidirectional"))
    )
    (net (code "80") (name "unconnected-(MCU1-PadPGM)") (class "Default")
      (node (ref "MCU1") (pin "PGM") (pinfunction "PGM_PGM") (pintype "bidirectional"))
    )
    (net (code "81") (name "unconnected-(MCU1-PadRESET)") (class "Default")
      (node (ref "MCU1") (pin "RESET") (pinfunction "RESET_RESET") (pintype "bidirectional"))
    )
    (net (code "82") (name "unconnected-(U$1-Pad1)") (class "Default")
      (node (ref "U$1") (pin "1") (pinfunction "1_1") (pintype "bidirectional"))
    )
    (net (code "83") (name "unconnected-(U$2-4OUT-Pad14)") (class "Default")
      (node (ref "U$2") (pin "14") (pinfunction "4OUT_14") (pintype "bidirectional"))
    )
    (net (code "84") (name "unconnected-(U$14-Pad6)") (class "Default")
      (node (ref "U$14") (pin "6") (pinfunction "6_6") (pintype "bidirectional"))
    )
    (net (code "85") (name "unconnected-(U$14-Pad7)") (class "Default")
      (node (ref "U$14") (pin "7") (pinfunction "7_7") (pintype "bidirectional"))
    )
    (net (code "86") (name "unconnected-(U$14-Pad8)") (class "Default")
      (node (ref "U$14") (pin "8") (pinfunction "8_8") (pintype "bidirectional"))
    )
  )
)
